# BeltBoard.net
KiCad netlist of a schematic drawn in EAGLE
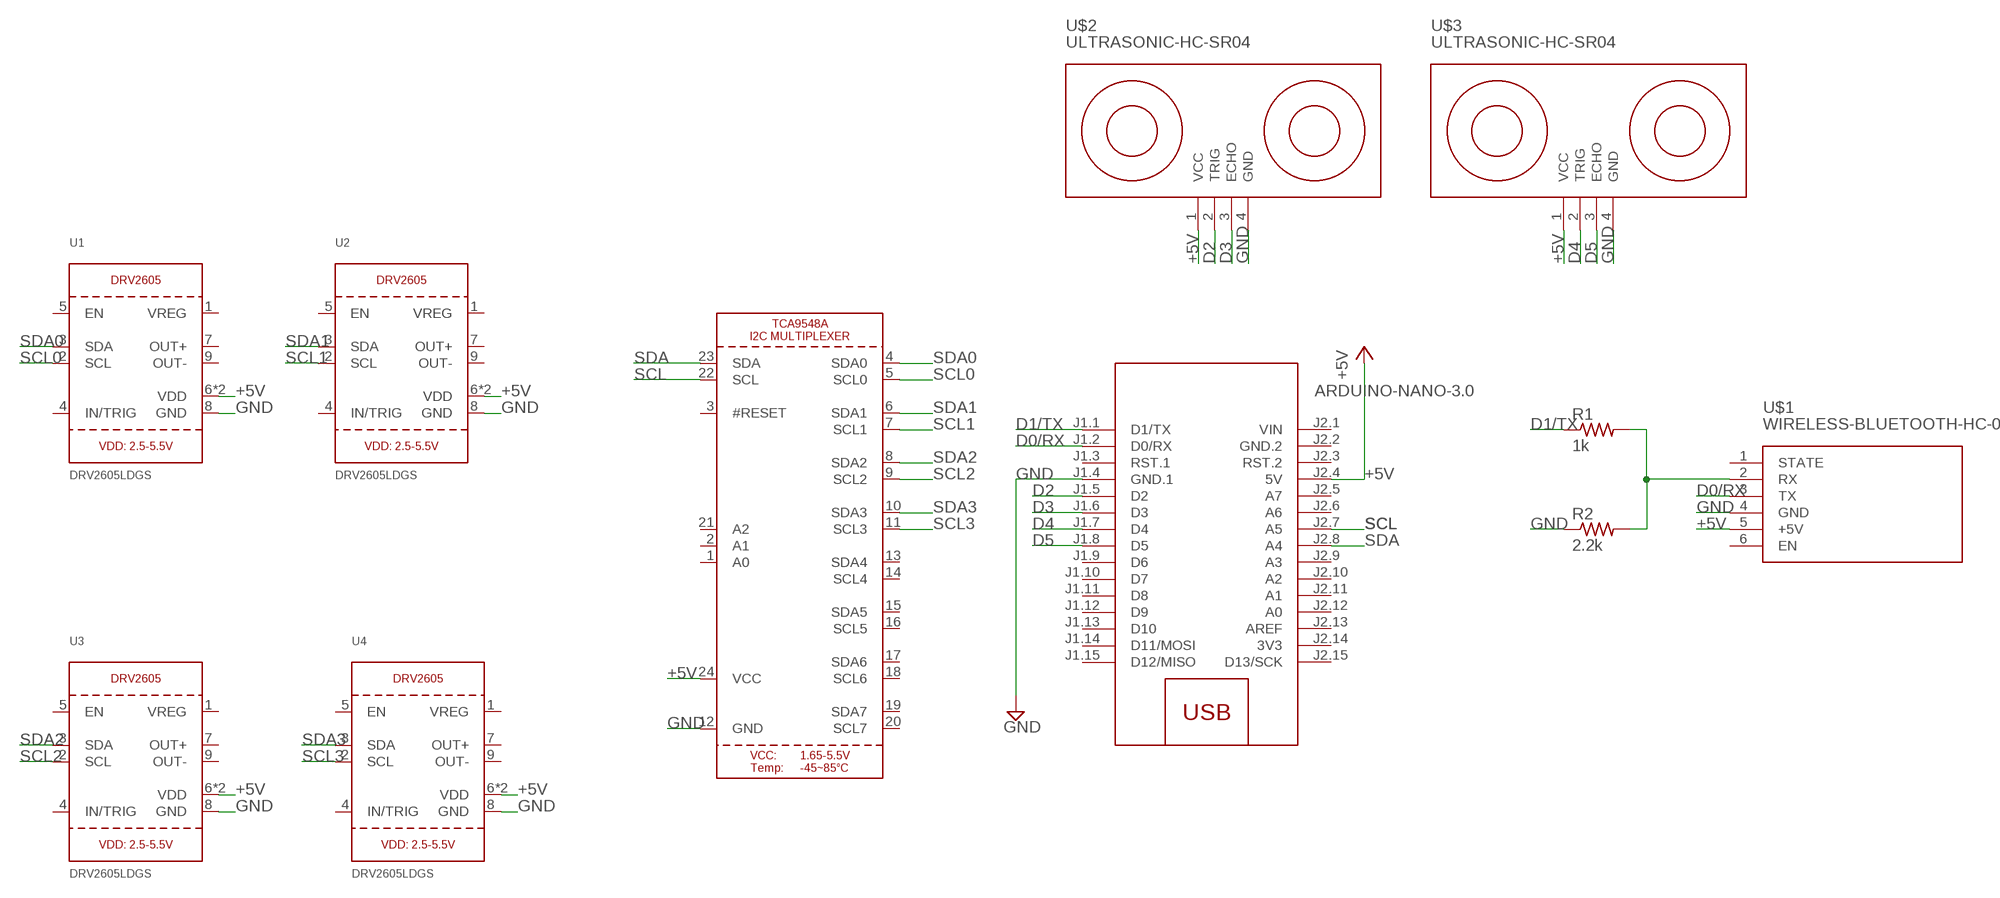
[diagram p0: schematic, sheet 1]

(export (version "E")
  (design (tool "Eeschema 10.0.6"))
  (components
    (comp (ref "M1")
      (value "ARDUINO-NANO-3.0")
      (footprint "eagle-import:ARDUINO-NANO-3.0")
      (libsource (lib "eagle-import") (part "ARDUINO-NANO-3.0"))
    )
    (comp (ref "R1")
      (value "1k")
      (footprint "eagle-import:R0805")
      (libsource (lib "eagle-import") (part "R-US_R0805"))
    )
    (comp (ref "R2")
      (value "2.2k")
      (footprint "eagle-import:R0805")
      (libsource (lib "eagle-import") (part "R-US_R0805"))
    )
    (comp (ref "U$1")
      (value "WIRELESS-BLUETOOTH-HC-05")
      (footprint "eagle-import:WIRELESS-BLUETOOTH-HC-05")
      (libsource (lib "eagle-import") (part "WIRELESS-BLUETOOTH-HC-05"))
    )
    (comp (ref "U$2")
      (value "ULTRASONIC-HC-SR04")
      (footprint "eagle-import:ULTRASONIC-HC-SR04")
      (libsource (lib "eagle-import") (part "ULTRASONIC-HC-SR04"))
    )
    (comp (ref "U$3")
      (value "ULTRASONIC-HC-SR04")
      (footprint "eagle-import:ULTRASONIC-HC-SR04")
      (libsource (lib "eagle-import") (part "ULTRASONIC-HC-SR04"))
    )
    (comp (ref "U1")
      (value "DRV2605LDGS")
      (footprint "eagle-import:PSOP10")
      (libsource (lib "eagle-import") (part "DRV2605_SOP"))
    )
    (comp (ref "U2")
      (value "DRV2605LDGS")
      (footprint "eagle-import:PSOP10")
      (libsource (lib "eagle-import") (part "DRV2605_SOP"))
    )
    (comp (ref "U3")
      (value "DRV2605LDGS")
      (footprint "eagle-import:PSOP10")
      (libsource (lib "eagle-import") (part "DRV2605_SOP"))
    )
    (comp (ref "U4")
      (value "DRV2605LDGS")
      (footprint "eagle-import:PSOP10")
      (libsource (lib "eagle-import") (part "DRV2605_SOP"))
    )
    (comp (ref "U5")
      (value "TCA9548APWR")
      (footprint "eagle-import:TSSOP24")
      (libsource (lib "eagle-import") (part "TCA9548A"))
    )
  )
  (nets
    (net (code "1") (name "+5V") (class "Default")
      (node (ref "M1") (pin "J2.4") (pinfunction "5V_J2.4") (pintype "power_in"))
      (node (ref "U$1") (pin "5") (pinfunction "+5V_5") (pintype "power_in"))
      (node (ref "U$2") (pin "1") (pinfunction "VCC_1") (pintype "power_in"))
      (node (ref "U$3") (pin "1") (pinfunction "VCC_1") (pintype "power_in"))
      (node (ref "U1") (pin "10") (pinfunction "VDD_10") (pintype "power_in"))
      (node (ref "U1") (pin "6") (pinfunction "VDD_6") (pintype "power_in"))
      (node (ref "U2") (pin "10") (pinfunction "VDD_10") (pintype "power_in"))
      (node (ref "U2") (pin "6") (pinfunction "VDD_6") (pintype "power_in"))
      (node (ref "U3") (pin "10") (pinfunction "VDD_10") (pintype "power_in"))
      (node (ref "U3") (pin "6") (pinfunction "VDD_6") (pintype "power_in"))
      (node (ref "U4") (pin "10") (pinfunction "VDD_10") (pintype "power_in"))
      (node (ref "U4") (pin "6") (pinfunction "VDD_6") (pintype "power_in"))
      (node (ref "U5") (pin "24") (pinfunction "VCC_24") (pintype "bidirectional"))
    )
    (net (code "2") (name "/3V3") (class "Default")
      (node (ref "M1") (pin "J2.14") (pinfunction "3V3_J2.14") (pintype "power_in"))
    )
    (net (code "3") (name "/D0{slash}RX") (class "Default")
      (node (ref "M1") (pin "J1.2") (pinfunction "D0/RX_J1.2") (pintype "bidirectional"))
      (node (ref "U$1") (pin "3") (pinfunction "TX_3") (pintype "bidirectional"))
    )
    (net (code "4") (name "/D1{slash}TX") (class "Default")
      (node (ref "M1") (pin "J1.1") (pinfunction "D1/TX_J1.1") (pintype "bidirectional"))
      (node (ref "R1") (pin "1") (pinfunction "1_1") (pintype "passive"))
    )
    (net (code "5") (name "/D2") (class "Default")
      (node (ref "M1") (pin "J1.5") (pinfunction "D2_J1.5") (pintype "bidirectional"))
      (node (ref "U$2") (pin "2") (pinfunction "TRIG_2") (pintype "input"))
    )
    (net (code "6") (name "/D3") (class "Default")
      (node (ref "M1") (pin "J1.6") (pinfunction "D3_J1.6") (pintype "bidirectional"))
      (node (ref "U$2") (pin "3") (pinfunction "ECHO_3") (pintype "output"))
    )
    (net (code "7") (name "/D4") (class "Default")
      (node (ref "M1") (pin "J1.7") (pinfunction "D4_J1.7") (pintype "bidirectional"))
      (node (ref "U$3") (pin "2") (pinfunction "TRIG_2") (pintype "input"))
    )
    (net (code "8") (name "/D5") (class "Default")
      (node (ref "M1") (pin "J1.8") (pinfunction "D5_J1.8") (pintype "bidirectional"))
      (node (ref "U$3") (pin "3") (pinfunction "ECHO_3") (pintype "output"))
    )
    (net (code "9") (name "/GND.2") (class "Default")
      (node (ref "M1") (pin "J2.2") (pinfunction "GND.2_J2.2") (pintype "power_in"))
    )
    (net (code "10") (name "/SCL") (class "Default")
      (node (ref "M1") (pin "J2.7") (pinfunction "A5_J2.7") (pintype "bidirectional"))
      (node (ref "U5") (pin "22") (pinfunction "SCL_22") (pintype "bidirectional"))
    )
    (net (code "11") (name "/SCL0") (class "Default")
      (node (ref "U1") (pin "2") (pinfunction "SCL_2") (pintype "input"))
      (node (ref "U5") (pin "5") (pinfunction "SCL0_5") (pintype "bidirectional"))
    )
    (net (code "12") (name "/SCL1") (class "Default")
      (node (ref "U2") (pin "2") (pinfunction "SCL_2") (pintype "input"))
      (node (ref "U5") (pin "7") (pinfunction "SCL1_7") (pintype "bidirectional"))
    )
    (net (code "13") (name "/SCL2") (class "Default")
      (node (ref "U3") (pin "2") (pinfunction "SCL_2") (pintype "input"))
      (node (ref "U5") (pin "9") (pinfunction "SCL2_9") (pintype "bidirectional"))
    )
    (net (code "14") (name "/SCL3") (class "Default")
      (node (ref "U4") (pin "2") (pinfunction "SCL_2") (pintype "input"))
      (node (ref "U5") (pin "11") (pinfunction "SCL3_11") (pintype "bidirectional"))
    )
    (net (code "15") (name "/SDA") (class "Default")
      (node (ref "M1") (pin "J2.8") (pinfunction "A4_J2.8") (pintype "bidirectional"))
      (node (ref "U5") (pin "23") (pinfunction "SDA_23") (pintype "bidirectional"))
    )
    (net (code "16") (name "/SDA0") (class "Default")
      (node (ref "U1") (pin "3") (pinfunction "SDA_3") (pintype "bidirectional"))
      (node (ref "U5") (pin "4") (pinfunction "SDA0_4") (pintype "bidirectional"))
    )
    (net (code "17") (name "/SDA1") (class "Default")
      (node (ref "U2") (pin "3") (pinfunction "SDA_3") (pintype "bidirectional"))
      (node (ref "U5") (pin "6") (pinfunction "SDA1_6") (pintype "bidirectional"))
    )
    (net (code "18") (name "/SDA2") (class "Default")
      (node (ref "U3") (pin "3") (pinfunction "SDA_3") (pintype "bidirectional"))
      (node (ref "U5") (pin "8") (pinfunction "SDA2_8") (pintype "bidirectional"))
    )
    (net (code "19") (name "/SDA3") (class "Default")
      (node (ref "U4") (pin "3") (pinfunction "SDA_3") (pintype "bidirectional"))
      (node (ref "U5") (pin "10") (pinfunction "SDA3_10") (pintype "bidirectional"))
    )
    (net (code "20") (name "/VIN") (class "Default")
      (node (ref "M1") (pin "J2.1") (pinfunction "VIN_J2.1") (pintype "power_in"))
    )
    (net (code "21") (name "GND") (class "Default")
      (node (ref "M1") (pin "J1.4") (pinfunction "GND.1_J1.4") (pintype "power_in"))
      (node (ref "R2") (pin "1") (pinfunction "1_1") (pintype "passive"))
      (node (ref "U$1") (pin "4") (pinfunction "GND_4") (pintype "power_in"))
      (node (ref "U$2") (pin "4") (pinfunction "GND_4") (pintype "power_in"))
      (node (ref "U$3") (pin "4") (pinfunction "GND_4") (pintype "power_in"))
      (node (ref "U1") (pin "8") (pinfunction "GND_8") (pintype "power_in"))
      (node (ref "U2") (pin "8") (pinfunction "GND_8") (pintype "power_in"))
      (node (ref "U3") (pin "8") (pinfunction "GND_8") (pintype "power_in"))
      (node (ref "U4") (pin "8") (pinfunction "GND_8") (pintype "power_in"))
      (node (ref "U5") (pin "12") (pinfunction "GND_12") (pintype "bidirectional"))
    )
    (net (code "22") (name "Net-(U$1-RX)") (class "Default")
      (node (ref "R1") (pin "2") (pinfunction "2_2") (pintype "passive"))
      (node (ref "R2") (pin "2") (pinfunction "2_2") (pintype "passive"))
      (node (ref "U$1") (pin "2") (pinfunction "RX_2") (pintype "bidirectional"))
    )
    (net (code "23") (name "unconnected-(M1-A0-PadJ2.12)") (class "Default")
      (node (ref "M1") (pin "J2.12") (pinfunction "A0_J2.12") (pintype "bidirectional"))
    )
    (net (code "24") (name "unconnected-(M1-A1-PadJ2.11)") (class "Default")
      (node (ref "M1") (pin "J2.11") (pinfunction "A1_J2.11") (pintype "bidirectional"))
    )
    (net (code "25") (name "unconnected-(M1-A2-PadJ2.10)") (class "Default")
      (node (ref "M1") (pin "J2.10") (pinfunction "A2_J2.10") (pintype "bidirectional"))
    )
    (net (code "26") (name "unconnected-(M1-A3-PadJ2.9)") (class "Default")
      (node (ref "M1") (pin "J2.9") (pinfunction "A3_J2.9") (pintype "bidirectional"))
    )
    (net (code "27") (name "unconnected-(M1-A6-PadJ2.6)") (class "Default")
      (node (ref "M1") (pin "J2.6") (pinfunction "A6_J2.6") (pintype "bidirectional"))
    )
    (net (code "28") (name "unconnected-(M1-A7-PadJ2.5)") (class "Default")
      (node (ref "M1") (pin "J2.5") (pinfunction "A7_J2.5") (pintype "bidirectional"))
    )
    (net (code "29") (name "unconnected-(M1-AREF-PadJ2.13)") (class "Default")
      (node (ref "M1") (pin "J2.13") (pinfunction "AREF_J2.13") (pintype "bidirectional"))
    )
    (net (code "30") (name "unconnected-(M1-D6-PadJ1.9)") (class "Default")
      (node (ref "M1") (pin "J1.9") (pinfunction "D6_J1.9") (pintype "bidirectional"))
    )
    (net (code "31") (name "unconnected-(M1-D7-PadJ1.10)") (class "Default")
      (node (ref "M1") (pin "J1.10") (pinfunction "D7_J1.10") (pintype "bidirectional"))
    )
    (net (code "32") (name "unconnected-(M1-D8-PadJ1.11)") (class "Default")
      (node (ref "M1") (pin "J1.11") (pinfunction "D8_J1.11") (pintype "bidirectional"))
    )
    (net (code "33") (name "unconnected-(M1-D9-PadJ1.12)") (class "Default")
      (node (ref "M1") (pin "J1.12") (pinfunction "D9_J1.12") (pintype "bidirectional"))
    )
    (net (code "34") (name "unconnected-(M1-D10-PadJ1.13)") (class "Default")
      (node (ref "M1") (pin "J1.13") (pinfunction "D10_J1.13") (pintype "bidirectional"))
    )
    (net (code "35") (name "unconnected-(M1-D11{slash}MOSI-PadJ1.14)") (class "Default")
      (node (ref "M1") (pin "J1.14") (pinfunction "D11/MOSI_J1.14") (pintype "bidirectional"))
    )
    (net (code "36") (name "unconnected-(M1-D12{slash}MISO-PadJ1.15)") (class "Default")
      (node (ref "M1") (pin "J1.15") (pinfunction "D12/MISO_J1.15") (pintype "bidirectional"))
    )
    (net (code "37") (name "unconnected-(M1-D13{slash}SCK-PadJ2.15)") (class "Default")
      (node (ref "M1") (pin "J2.15") (pinfunction "D13/SCK_J2.15") (pintype "bidirectional"))
    )
    (net (code "38") (name "unconnected-(M1-RST.1-PadJ1.3)") (class "Default")
      (node (ref "M1") (pin "J1.3") (pinfunction "RST.1_J1.3") (pintype "bidirectional"))
    )
    (net (code "39") (name "unconnected-(M1-RST.2-PadJ2.3)") (class "Default")
      (node (ref "M1") (pin "J2.3") (pinfunction "RST.2_J2.3") (pintype "bidirectional"))
    )
    (net (code "40") (name "unconnected-(U$1-EN-Pad6)") (class "Default")
      (node (ref "U$1") (pin "6") (pinfunction "EN_6") (pintype "bidirectional"))
    )
    (net (code "41") (name "unconnected-(U$1-STATE-Pad1)") (class "Default")
      (node (ref "U$1") (pin "1") (pinfunction "STATE_1") (pintype "bidirectional"))
    )
    (net (code "42") (name "unconnected-(U1-EN-Pad5)") (class "Default")
      (node (ref "U1") (pin "5") (pinfunction "EN_5") (pintype "input"))
    )
    (net (code "43") (name "unconnected-(U1-IN{slash}TRIG-Pad4)") (class "Default")
      (node (ref "U1") (pin "4") (pinfunction "IN/TRIG_4") (pintype "input"))
    )
    (net (code "44") (name "unconnected-(U1-OUT+-Pad7)") (class "Default")
      (node (ref "U1") (pin "7") (pinfunction "OUT+_7") (pintype "output"))
    )
    (net (code "45") (name "unconnected-(U1-OUT--Pad9)") (class "Default")
      (node (ref "U1") (pin "9") (pinfunction "OUT-_9") (pintype "output"))
    )
    (net (code "46") (name "unconnected-(U1-VREG-Pad1)") (class "Default")
      (node (ref "U1") (pin "1") (pinfunction "VREG_1") (pintype "output"))
    )
    (net (code "47") (name "unconnected-(U2-EN-Pad5)") (class "Default")
      (node (ref "U2") (pin "5") (pinfunction "EN_5") (pintype "input"))
    )
    (net (code "48") (name "unconnected-(U2-IN{slash}TRIG-Pad4)") (class "Default")
      (node (ref "U2") (pin "4") (pinfunction "IN/TRIG_4") (pintype "input"))
    )
    (net (code "49") (name "unconnected-(U2-OUT+-Pad7)") (class "Default")
      (node (ref "U2") (pin "7") (pinfunction "OUT+_7") (pintype "output"))
    )
    (net (code "50") (name "unconnected-(U2-OUT--Pad9)") (class "Default")
      (node (ref "U2") (pin "9") (pinfunction "OUT-_9") (pintype "output"))
    )
    (net (code "51") (name "unconnected-(U2-VREG-Pad1)") (class "Default")
      (node (ref "U2") (pin "1") (pinfunction "VREG_1") (pintype "output"))
    )
    (net (code "52") (name "unconnected-(U3-EN-Pad5)") (class "Default")
      (node (ref "U3") (pin "5") (pinfunction "EN_5") (pintype "input"))
    )
    (net (code "53") (name "unconnected-(U3-IN{slash}TRIG-Pad4)") (class "Default")
      (node (ref "U3") (pin "4") (pinfunction "IN/TRIG_4") (pintype "input"))
    )
    (net (code "54") (name "unconnected-(U3-OUT+-Pad7)") (class "Default")
      (node (ref "U3") (pin "7") (pinfunction "OUT+_7") (pintype "output"))
    )
    (net (code "55") (name "unconnected-(U3-OUT--Pad9)") (class "Default")
      (node (ref "U3") (pin "9") (pinfunction "OUT-_9") (pintype "output"))
    )
    (net (code "56") (name "unconnected-(U3-VREG-Pad1)") (class "Default")
      (node (ref "U3") (pin "1") (pinfunction "VREG_1") (pintype "output"))
    )
    (net (code "57") (name "unconnected-(U4-EN-Pad5)") (class "Default")
      (node (ref "U4") (pin "5") (pinfunction "EN_5") (pintype "input"))
    )
    (net (code "58") (name "unconnected-(U4-IN{slash}TRIG-Pad4)") (class "Default")
      (node (ref "U4") (pin "4") (pinfunction "IN/TRIG_4") (pintype "input"))
    )
    (net (code "59") (name "unconnected-(U4-OUT+-Pad7)") (class "Default")
      (node (ref "U4") (pin "7") (pinfunction "OUT+_7") (pintype "output"))
    )
    (net (code "60") (name "unconnected-(U4-OUT--Pad9)") (class "Default")
      (node (ref "U4") (pin "9") (pinfunction "OUT-_9") (pintype "output"))
    )
    (net (code "61") (name "unconnected-(U4-VREG-Pad1)") (class "Default")
      (node (ref "U4") (pin "1") (pinfunction "VREG_1") (pintype "output"))
    )
    (net (code "62") (name "unconnected-(U5-#RESET-Pad3)") (class "Default")
      (node (ref "U5") (pin "3") (pinfunction "#RESET_3") (pintype "bidirectional"))
    )
    (net (code "63") (name "unconnected-(U5-A0-Pad1)") (class "Default")
      (node (ref "U5") (pin "1") (pinfunction "A0_1") (pintype "bidirectional"))
    )
    (net (code "64") (name "unconnected-(U5-A1-Pad2)") (class "Default")
      (node (ref "U5") (pin "2") (pinfunction "A1_2") (pintype "bidirectional"))
    )
    (net (code "65") (name "unconnected-(U5-A2-Pad21)") (class "Default")
      (node (ref "U5") (pin "21") (pinfunction "A2_21") (pintype "bidirectional"))
    )
    (net (code "66") (name "unconnected-(U5-SCL4-Pad14)") (class "Default")
      (node (ref "U5") (pin "14") (pinfunction "SCL4_14") (pintype "bidirectional"))
    )
    (net (code "67") (name "unconnected-(U5-SCL5-Pad16)") (class "Default")
      (node (ref "U5") (pin "16") (pinfunction "SCL5_16") (pintype "bidirectional"))
    )
    (net (code "68") (name "unconnected-(U5-SCL6-Pad18)") (class "Default")
      (node (ref "U5") (pin "18") (pinfunction "SCL6_18") (pintype "bidirectional"))
    )
    (net (code "69") (name "unconnected-(U5-SCL7-Pad20)") (class "Default")
      (node (ref "U5") (pin "20") (pinfunction "SCL7_20") (pintype "bidirectional"))
    )
    (net (code "70") (name "unconnected-(U5-SDA4-Pad13)") (class "Default")
      (node (ref "U5") (pin "13") (pinfunction "SDA4_13") (pintype "bidirectional"))
    )
    (net (code "71") (name "unconnected-(U5-SDA5-Pad15)") (class "Default")
      (node (ref "U5") (pin "15") (pinfunction "SDA5_15") (pintype "bidirectional"))
    )
    (net (code "72") (name "unconnected-(U5-SDA6-Pad17)") (class "Default")
      (node (ref "U5") (pin "17") (pinfunction "SDA6_17") (pintype "bidirectional"))
    )
    (net (code "73") (name "unconnected-(U5-SDA7-Pad19)") (class "Default")
      (node (ref "U5") (pin "19") (pinfunction "SDA7_19") (pintype "bidirectional"))
    )
  )
)
